# Page_08-Strap_LEDs.net
KiCad netlist of a schematic drawn in Altium Designer
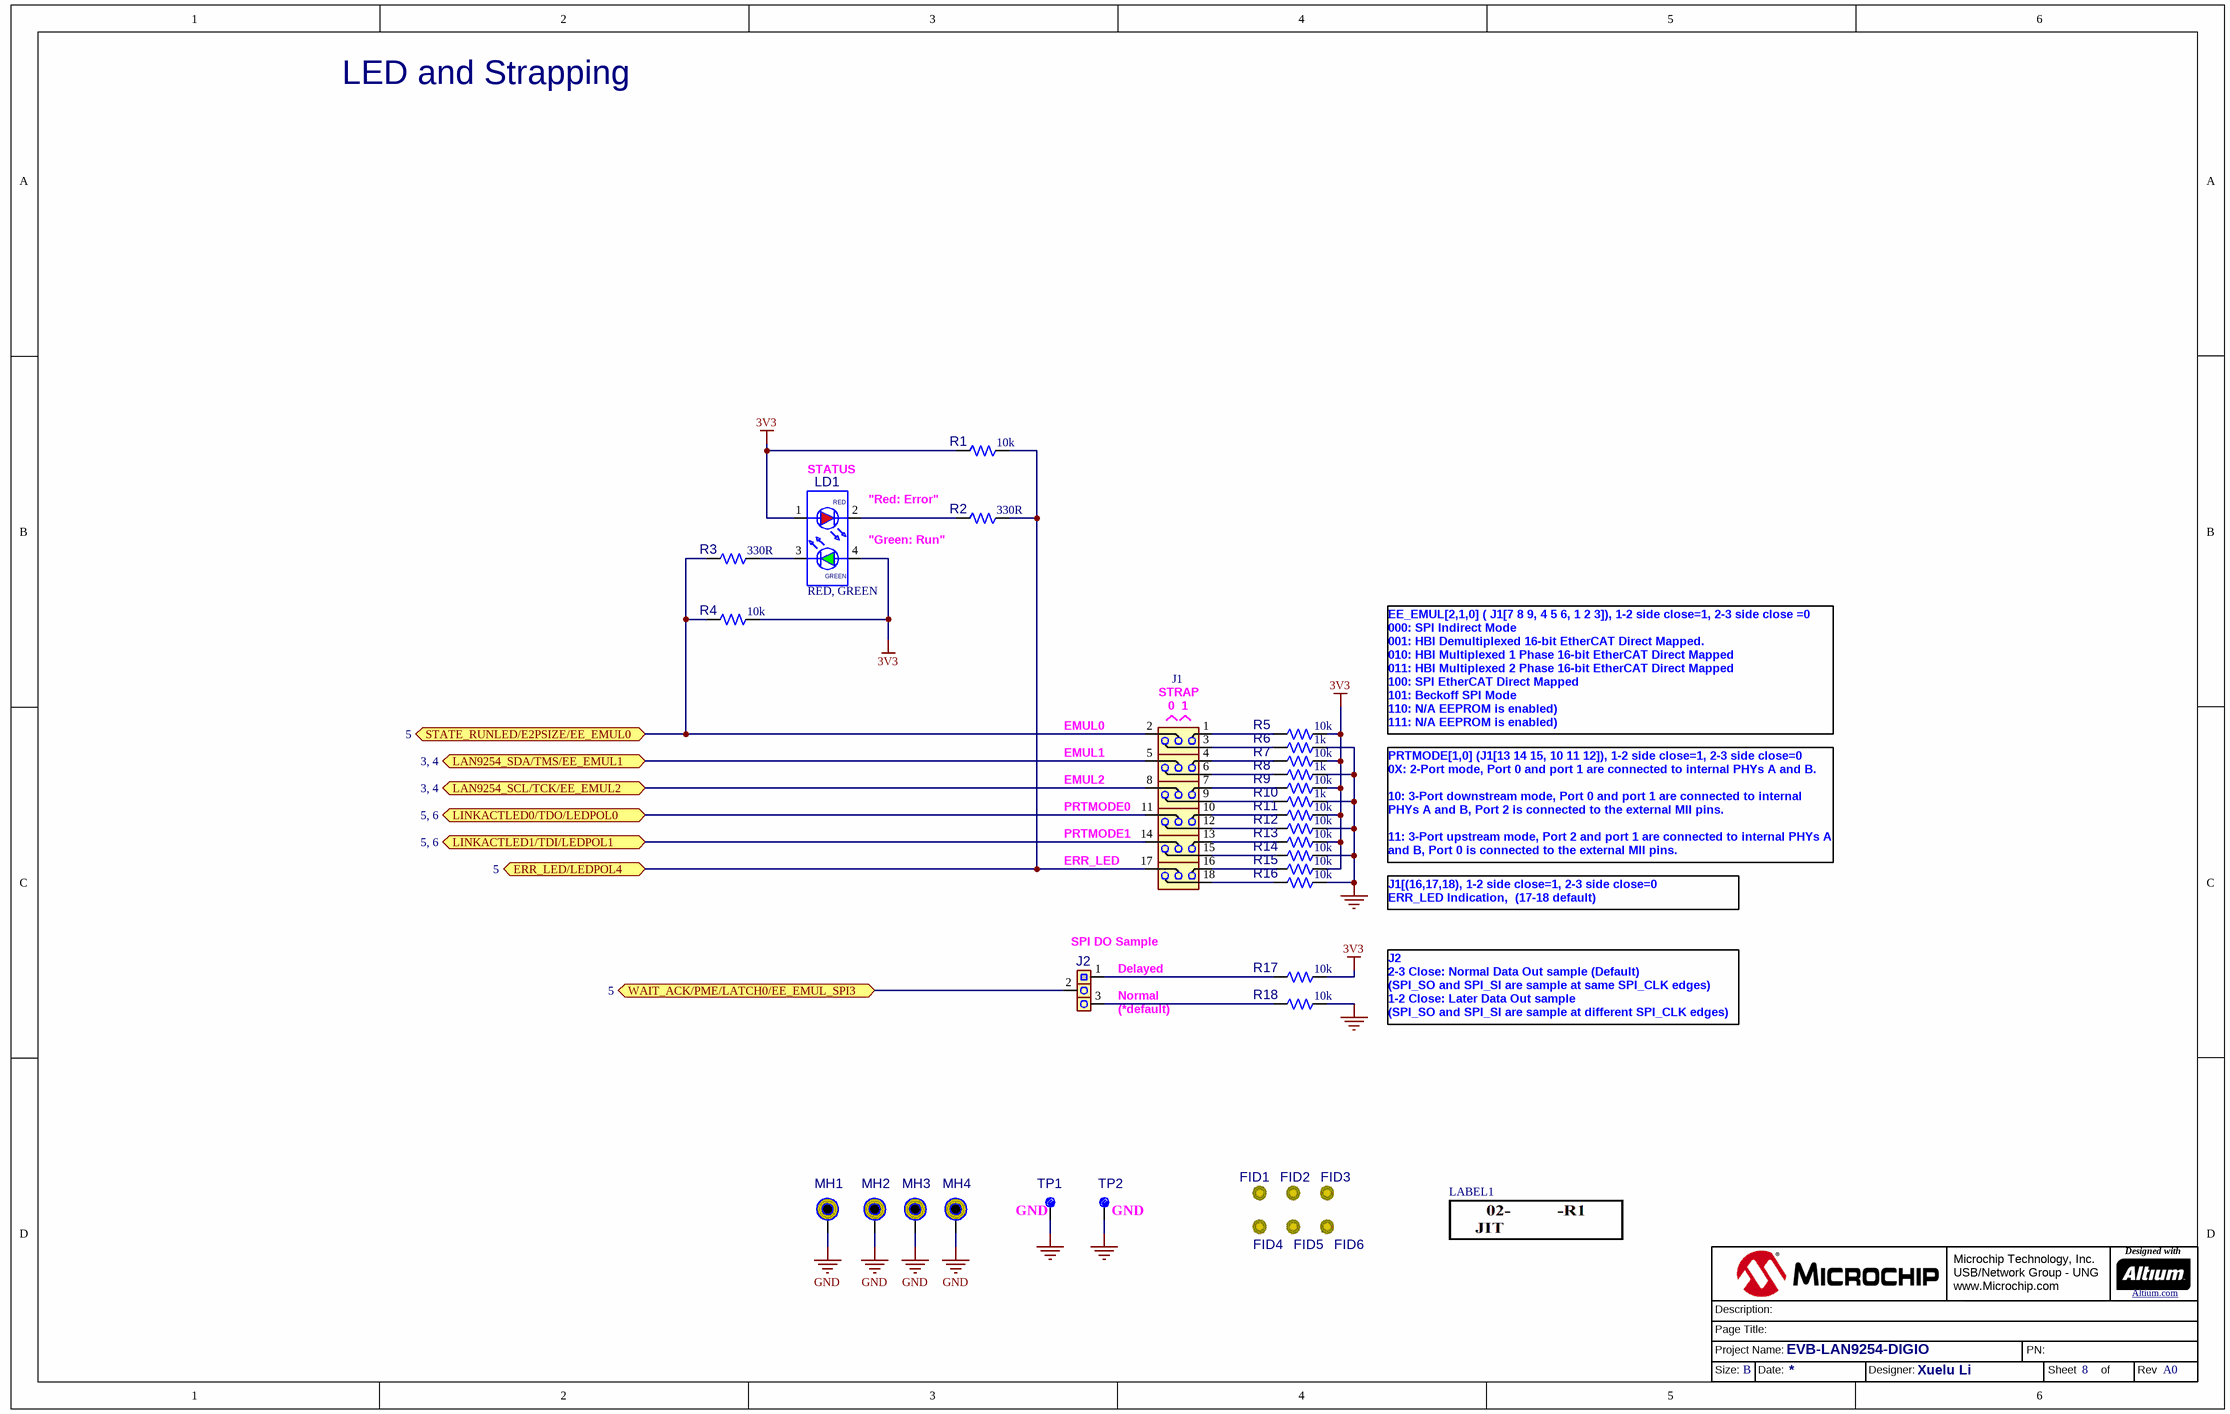
[diagram p0: Page 08-Strap&LEDs.SchDoc]

(export (version "E")
  (design (tool "Eeschema 10.0.6"))
  (components
    (comp (ref "FID1")
      (value "FIDUCIAL")
      (footprint "FIDUCIAL")
      (libsource (lib "UNG_MISC") (part "FIDUCIAL"))
    )
    (comp (ref "FID2")
      (value "FIDUCIAL")
      (footprint "FIDUCIAL")
      (libsource (lib "UNG_MISC") (part "FIDUCIAL"))
    )
    (comp (ref "FID3")
      (value "FIDUCIAL")
      (footprint "FIDUCIAL")
      (libsource (lib "UNG_MISC") (part "FIDUCIAL"))
    )
    (comp (ref "FID4")
      (value "FIDUCIAL")
      (footprint "FIDUCIAL")
      (libsource (lib "UNG_MISC") (part "FIDUCIAL"))
    )
    (comp (ref "FID5")
      (value "FIDUCIAL")
      (footprint "FIDUCIAL")
      (libsource (lib "UNG_MISC") (part "FIDUCIAL"))
    )
    (comp (ref "FID6")
      (value "FIDUCIAL")
      (footprint "FIDUCIAL")
      (libsource (lib "UNG_MISC") (part "FIDUCIAL"))
    )
    (comp (ref "J1")
      (value "Header 3X6")
      (footprint "HDR_M_2.54_3X6")
      (fields (field (name "OWNER") "Manikandan Balakrishnan"))
      (libsource (lib "MCHP-CDB") (part "Header 3X6"))
    )
    (comp (ref "J2")
      (value "Header 1x3")
      (footprint "HDR_M_2.54_1x3")
      (libsource (lib "MCHP-CDB") (part "Header 1x3"))
    )
    (comp (ref "LABEL1")
      (value "LABEL_Need_Help_Small")
      (footprint "LABEL_Need_Help_Small")
      (libsource (lib "MCHP-CDB") (part "LABEL_Need_Help_Small"))
    )
    (comp (ref "LD1")
      (value "RED, GREEN")
      (footprint "LED_DUAL_SMD_2x1.25mm")
      (description "LED")
      (fields
        (field (name "POWER") "75mW")
        (field (name "Comment") "LED DUAL 4 pin")
        (field (name "OWNER") "Bogdan P (M91398)")
      )
      (libsource (lib "MCHP-CDB") (part "LED DUAL 4 pin"))
    )
    (comp (ref "MH1")
      (value "MTHOLE 4-40 120DL 220PAD")
      (footprint "MTHOLE_4-40")
      (libsource (lib "UNG_MISC") (part "MTHOLE 4-40 120DL 220PAD"))
    )
    (comp (ref "MH2")
      (value "MTHOLE 4-40 120DL 220PAD")
      (footprint "MTHOLE_4-40")
      (libsource (lib "UNG_MISC") (part "MTHOLE 4-40 120DL 220PAD"))
    )
    (comp (ref "MH3")
      (value "MTHOLE 4-40 120DL 220PAD")
      (footprint "MTHOLE_4-40")
      (libsource (lib "UNG_MISC") (part "MTHOLE 4-40 120DL 220PAD"))
    )
    (comp (ref "MH4")
      (value "MTHOLE 4-40 120DL 220PAD")
      (footprint "MTHOLE_4-40")
      (libsource (lib "UNG_MISC") (part "MTHOLE 4-40 120DL 220PAD"))
    )
    (comp (ref "R1")
      (value "10k")
      (footprint "RES_C_0603")
      (description "Resistor")
      (fields (field (name "TOLERANCE") "1%") (field (name "POWER") "1/10W"))
      (libsource (lib "MCHP-CDB") (part "Resistor"))
    )
    (comp (ref "R2")
      (value "330R")
      (footprint "RES_C_0603")
      (description "Resistor")
      (fields (field (name "TOLERANCE") "5%") (field (name "VOLTAGE") "50V"))
      (libsource (lib "MCHP-CDB") (part "Resistor"))
    )
    (comp (ref "R3")
      (value "330R")
      (footprint "RES_C_0603")
      (description "Resistor")
      (fields (field (name "TOLERANCE") "5%") (field (name "VOLTAGE") "50V"))
      (libsource (lib "MCHP-CDB") (part "Resistor"))
    )
    (comp (ref "R4")
      (value "10k")
      (footprint "RES_C_0603")
      (description "Resistor")
      (fields (field (name "TOLERANCE") "1%") (field (name "POWER") "1/10W"))
      (libsource (lib "MCHP-CDB") (part "Resistor"))
    )
    (comp (ref "R5")
      (value "10k")
      (footprint "RES_C_0603")
      (description "Resistor")
      (fields (field (name "TOLERANCE") "1%") (field (name "POWER") "1/10W"))
      (libsource (lib "MCHP-CDB") (part "Resistor"))
    )
    (comp (ref "R6")
      (value "1k")
      (footprint "RES_C_0603")
      (description "Resistor")
      (fields
        (field (name "TOLERANCE") "5%")
        (field (name "VOLTAGE") "75V")
        (field (name "OWNER") "Bogdan P (M91398)")
      )
      (libsource (lib "MCHP-CDB") (part "Resistor"))
    )
    (comp (ref "R7")
      (value "10k")
      (footprint "RES_C_0603")
      (description "Resistor")
      (fields (field (name "TOLERANCE") "1%") (field (name "POWER") "1/10W"))
      (libsource (lib "MCHP-CDB") (part "Resistor"))
    )
    (comp (ref "R8")
      (value "1k")
      (footprint "RES_C_0603")
      (description "Resistor")
      (fields
        (field (name "TOLERANCE") "5%")
        (field (name "VOLTAGE") "75V")
        (field (name "OWNER") "Bogdan P (M91398)")
      )
      (libsource (lib "MCHP-CDB") (part "Resistor"))
    )
    (comp (ref "R9")
      (value "10k")
      (footprint "RES_C_0603")
      (description "Resistor")
      (fields (field (name "TOLERANCE") "1%") (field (name "POWER") "1/10W"))
      (libsource (lib "MCHP-CDB") (part "Resistor"))
    )
    (comp (ref "R10")
      (value "1k")
      (footprint "RES_C_0603")
      (description "Resistor")
      (fields
        (field (name "TOLERANCE") "5%")
        (field (name "VOLTAGE") "75V")
        (field (name "OWNER") "Bogdan P (M91398)")
      )
      (libsource (lib "MCHP-CDB") (part "Resistor"))
    )
    (comp (ref "R11")
      (value "10k")
      (footprint "RES_C_0603")
      (description "Resistor")
      (fields (field (name "TOLERANCE") "1%") (field (name "POWER") "1/10W"))
      (libsource (lib "MCHP-CDB") (part "Resistor"))
    )
    (comp (ref "R12")
      (value "10k")
      (footprint "RES_C_0603")
      (description "Resistor")
      (fields (field (name "TOLERANCE") "1%") (field (name "POWER") "1/10W"))
      (libsource (lib "MCHP-CDB") (part "Resistor"))
    )
    (comp (ref "R13")
      (value "10k")
      (footprint "RES_C_0603")
      (description "Resistor")
      (fields (field (name "TOLERANCE") "1%") (field (name "POWER") "1/10W"))
      (libsource (lib "MCHP-CDB") (part "Resistor"))
    )
    (comp (ref "R14")
      (value "10k")
      (footprint "RES_C_0603")
      (description "Resistor")
      (fields (field (name "TOLERANCE") "1%") (field (name "POWER") "1/10W"))
      (libsource (lib "MCHP-CDB") (part "Resistor"))
    )
    (comp (ref "R15")
      (value "10k")
      (footprint "RES_C_0603")
      (description "Resistor")
      (fields (field (name "TOLERANCE") "1%") (field (name "POWER") "1/10W"))
      (libsource (lib "MCHP-CDB") (part "Resistor"))
    )
    (comp (ref "R16")
      (value "10k")
      (footprint "RES_C_0603")
      (description "Resistor")
      (fields (field (name "TOLERANCE") "1%") (field (name "POWER") "1/10W"))
      (libsource (lib "MCHP-CDB") (part "Resistor"))
    )
    (comp (ref "R17")
      (value "10k")
      (footprint "RES_C_0603")
      (description "Resistor")
      (fields (field (name "TOLERANCE") "1%") (field (name "POWER") "1/10W"))
      (libsource (lib "MCHP-CDB") (part "Resistor"))
    )
    (comp (ref "R18")
      (value "10k")
      (footprint "RES_C_0603")
      (description "Resistor")
      (fields (field (name "TOLERANCE") "1%") (field (name "POWER") "1/10W"))
      (libsource (lib "MCHP-CDB") (part "Resistor"))
    )
    (comp (ref "TP1")
      (value "Test Point")
      (footprint "CON_TP_TH_V_BLK_KEC_5001")
      (fields (field (name "OWNER") "Stephen Humberd"))
      (libsource (lib "MCHP-CDB") (part "Test Point"))
    )
    (comp (ref "TP2")
      (value "Test Point")
      (footprint "CON_TP_TH_V_BLK_KEC_5001")
      (fields (field (name "OWNER") "Stephen Humberd"))
      (libsource (lib "MCHP-CDB") (part "Test Point"))
    )
  )
  (nets
    (net (code "1") (name "/ERR_LED{slash}LEDPOL4") (class "Default")
      (node (ref "J1") (pin "17") (pinfunction "17_17") (pintype "passive"))
      (node (ref "R1") (pin "2") (pinfunction "2_2") (pintype "passive"))
      (node (ref "R2") (pin "2") (pinfunction "2_2") (pintype "passive"))
    )
    (net (code "2") (name "/LAN9254_SCL{slash}TCK{slash}EE_EMUL2") (class "Default")
      (node (ref "J1") (pin "8") (pinfunction "8_8") (pintype "passive"))
    )
    (net (code "3") (name "/LAN9254_SDA{slash}TMS{slash}EE_EMUL1") (class "Default")
      (node (ref "J1") (pin "5") (pinfunction "5_5") (pintype "passive"))
    )
    (net (code "4") (name "/LINKACTLED0{slash}TDO{slash}LEDPOL0") (class "Default")
      (node (ref "J1") (pin "11") (pinfunction "11_11") (pintype "passive"))
    )
    (net (code "5") (name "/LINKACTLED1{slash}TDI{slash}LEDPOL1") (class "Default")
      (node (ref "J1") (pin "14") (pinfunction "14_14") (pintype "passive"))
    )
    (net (code "6") (name "/STATE_RUNLED{slash}E2PSIZE{slash}EE_EMUL0") (class "Default")
      (node (ref "J1") (pin "2") (pinfunction "2_2") (pintype "passive"))
      (node (ref "R3") (pin "1") (pinfunction "1_1") (pintype "passive"))
      (node (ref "R4") (pin "1") (pinfunction "1_1") (pintype "passive"))
    )
    (net (code "7") (name "/WAIT_ACK{slash}PME{slash}LATCH0{slash}EE_EMUL_SPI3") (class "Default")
      (node (ref "J2") (pin "2") (pinfunction "2_2") (pintype "passive"))
    )
    (net (code "8") (name "3V3") (class "Default")
      (node (ref "LD1") (pin "1") (pinfunction "A1_1") (pintype "passive"))
      (node (ref "LD1") (pin "4") (pinfunction "A2_4") (pintype "passive"))
      (node (ref "R1") (pin "1") (pinfunction "1_1") (pintype "passive"))
      (node (ref "R11") (pin "1") (pinfunction "1_1") (pintype "passive"))
      (node (ref "R13") (pin "1") (pinfunction "1_1") (pintype "passive"))
      (node (ref "R15") (pin "1") (pinfunction "1_1") (pintype "passive"))
      (node (ref "R17") (pin "1") (pinfunction "1_1") (pintype "passive"))
      (node (ref "R4") (pin "2") (pinfunction "2_2") (pintype "passive"))
      (node (ref "R5") (pin "1") (pinfunction "1_1") (pintype "passive"))
      (node (ref "R7") (pin "1") (pinfunction "1_1") (pintype "passive"))
      (node (ref "R9") (pin "1") (pinfunction "1_1") (pintype "passive"))
    )
    (net (code "9") (name "GND") (class "Default")
      (node (ref "MH1") (pin "1") (pinfunction "1_1") (pintype "passive"))
      (node (ref "MH2") (pin "1") (pinfunction "1_1") (pintype "passive"))
      (node (ref "MH3") (pin "1") (pinfunction "1_1") (pintype "passive"))
      (node (ref "MH4") (pin "1") (pinfunction "1_1") (pintype "passive"))
      (node (ref "R10") (pin "2") (pinfunction "2_2") (pintype "passive"))
      (node (ref "R12") (pin "1") (pinfunction "1_1") (pintype "passive"))
      (node (ref "R14") (pin "1") (pinfunction "1_1") (pintype "passive"))
      (node (ref "R16") (pin "1") (pinfunction "1_1") (pintype "passive"))
      (node (ref "R18") (pin "1") (pinfunction "1_1") (pintype "passive"))
      (node (ref "R6") (pin "2") (pinfunction "2_2") (pintype "passive"))
      (node (ref "R8") (pin "2") (pinfunction "2_2") (pintype "passive"))
      (node (ref "TP1") (pin "1") (pinfunction "1_1") (pintype "passive"))
      (node (ref "TP2") (pin "1") (pinfunction "1_1") (pintype "passive"))
    )
    (net (code "10") (name "Net-(J1-Pad1)") (class "Default")
      (node (ref "J1") (pin "1") (pinfunction "1_1") (pintype "passive"))
      (node (ref "R5") (pin "2") (pinfunction "2_2") (pintype "passive"))
    )
    (net (code "11") (name "Net-(J1-Pad3)") (class "Default")
      (node (ref "J1") (pin "3") (pinfunction "3_3") (pintype "passive"))
      (node (ref "R6") (pin "1") (pinfunction "1_1") (pintype "passive"))
    )
    (net (code "12") (name "Net-(J1-Pad4)") (class "Default")
      (node (ref "J1") (pin "4") (pinfunction "4_4") (pintype "passive"))
      (node (ref "R7") (pin "2") (pinfunction "2_2") (pintype "passive"))
    )
    (net (code "13") (name "Net-(J1-Pad6)") (class "Default")
      (node (ref "J1") (pin "6") (pinfunction "6_6") (pintype "passive"))
      (node (ref "R8") (pin "1") (pinfunction "1_1") (pintype "passive"))
    )
    (net (code "14") (name "Net-(J1-Pad7)") (class "Default")
      (node (ref "J1") (pin "7") (pinfunction "7_7") (pintype "passive"))
      (node (ref "R9") (pin "2") (pinfunction "2_2") (pintype "passive"))
    )
    (net (code "15") (name "Net-(J1-Pad9)") (class "Default")
      (node (ref "J1") (pin "9") (pinfunction "9_9") (pintype "passive"))
      (node (ref "R10") (pin "1") (pinfunction "1_1") (pintype "passive"))
    )
    (net (code "16") (name "Net-(J1-Pad10)") (class "Default")
      (node (ref "J1") (pin "10") (pinfunction "10_10") (pintype "passive"))
      (node (ref "R11") (pin "2") (pinfunction "2_2") (pintype "passive"))
    )
    (net (code "17") (name "Net-(J1-Pad12)") (class "Default")
      (node (ref "J1") (pin "12") (pinfunction "12_12") (pintype "passive"))
      (node (ref "R12") (pin "2") (pinfunction "2_2") (pintype "passive"))
    )
    (net (code "18") (name "Net-(J1-Pad13)") (class "Default")
      (node (ref "J1") (pin "13") (pinfunction "13_13") (pintype "passive"))
      (node (ref "R13") (pin "2") (pinfunction "2_2") (pintype "passive"))
    )
    (net (code "19") (name "Net-(J1-Pad15)") (class "Default")
      (node (ref "J1") (pin "15") (pinfunction "15_15") (pintype "passive"))
      (node (ref "R14") (pin "2") (pinfunction "2_2") (pintype "passive"))
    )
    (net (code "20") (name "Net-(J1-Pad16)") (class "Default")
      (node (ref "J1") (pin "16") (pinfunction "16_16") (pintype "passive"))
      (node (ref "R15") (pin "2") (pinfunction "2_2") (pintype "passive"))
    )
    (net (code "21") (name "Net-(J1-Pad18)") (class "Default")
      (node (ref "J1") (pin "18") (pinfunction "18_18") (pintype "passive"))
      (node (ref "R16") (pin "2") (pinfunction "2_2") (pintype "passive"))
    )
    (net (code "22") (name "Net-(J2-Pad1)") (class "Default")
      (node (ref "J2") (pin "1") (pinfunction "1_1") (pintype "passive"))
      (node (ref "R17") (pin "2") (pinfunction "2_2") (pintype "passive"))
    )
    (net (code "23") (name "Net-(J2-Pad3)") (class "Default")
      (node (ref "J2") (pin "3") (pinfunction "3_3") (pintype "passive"))
      (node (ref "R18") (pin "2") (pinfunction "2_2") (pintype "passive"))
    )
    (net (code "24") (name "Net-(LD1-K1)") (class "Default")
      (node (ref "LD1") (pin "2") (pinfunction "K1_2") (pintype "passive"))
      (node (ref "R2") (pin "1") (pinfunction "1_1") (pintype "passive"))
    )
    (net (code "25") (name "Net-(LD1-K2)") (class "Default")
      (node (ref "LD1") (pin "3") (pinfunction "K2_3") (pintype "passive"))
      (node (ref "R3") (pin "2") (pinfunction "2_2") (pintype "passive"))
    )
  )
)
